# Keyfinder_RF.net
KiCad netlist of a schematic drawn in Altium Designer
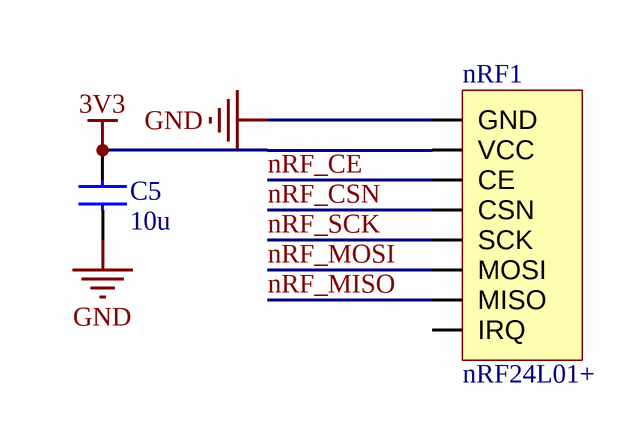
[diagram p0: Keyfinder_RF.SchDoc]

(export (version "E")
  (design (tool "Eeschema 10.0.6"))
  (components
    (comp (ref "C5")
      (value "10u")
      (footprint "0805_C")
      (description "Normaler Kondensator")
      (libsource (lib "MainBoard") (part "C?"))
    )
    (comp (ref "nRF1")
      (value "nRF24L01+")
      (footprint "CON_THT_2x4P_RM2.54_Stiftl")
      (libsource (lib "MainBoard") (part "Bluefruit"))
    )
  )
  (nets
    (net (code "1") (name "/nRF_CE") (class "Default")
      (node (ref "nRF1") (pin "3") (pinfunction "CE_3") (pintype "passive"))
    )
    (net (code "2") (name "/nRF_CSN") (class "Default")
      (node (ref "nRF1") (pin "4") (pinfunction "CSN_4") (pintype "passive"))
    )
    (net (code "3") (name "/nRF_MISO") (class "Default")
      (node (ref "nRF1") (pin "7") (pinfunction "MISO_7") (pintype "passive"))
    )
    (net (code "4") (name "/nRF_MOSI") (class "Default")
      (node (ref "nRF1") (pin "6") (pinfunction "MOSI_6") (pintype "passive"))
    )
    (net (code "5") (name "/nRF_SCK") (class "Default")
      (node (ref "nRF1") (pin "5") (pinfunction "SCK_5") (pintype "passive"))
    )
    (net (code "6") (name "3V3") (class "Default")
      (node (ref "C5") (pin "2") (pinfunction "2_2") (pintype "passive"))
      (node (ref "nRF1") (pin "2") (pinfunction "VCC_2") (pintype "passive"))
    )
    (net (code "7") (name "GND") (class "Default")
      (node (ref "C5") (pin "1") (pinfunction "1_1") (pintype "passive"))
      (node (ref "nRF1") (pin "1") (pinfunction "GND_1") (pintype "passive"))
    )
    (net (code "8") (name "unconnected-(nRF1-IRQ-Pad8)") (class "Default")
      (node (ref "nRF1") (pin "8") (pinfunction "IRQ_8") (pintype "passive"))
    )
  )
)
